# fiddle.net
KiCad netlist of a schematic drawn in EAGLE
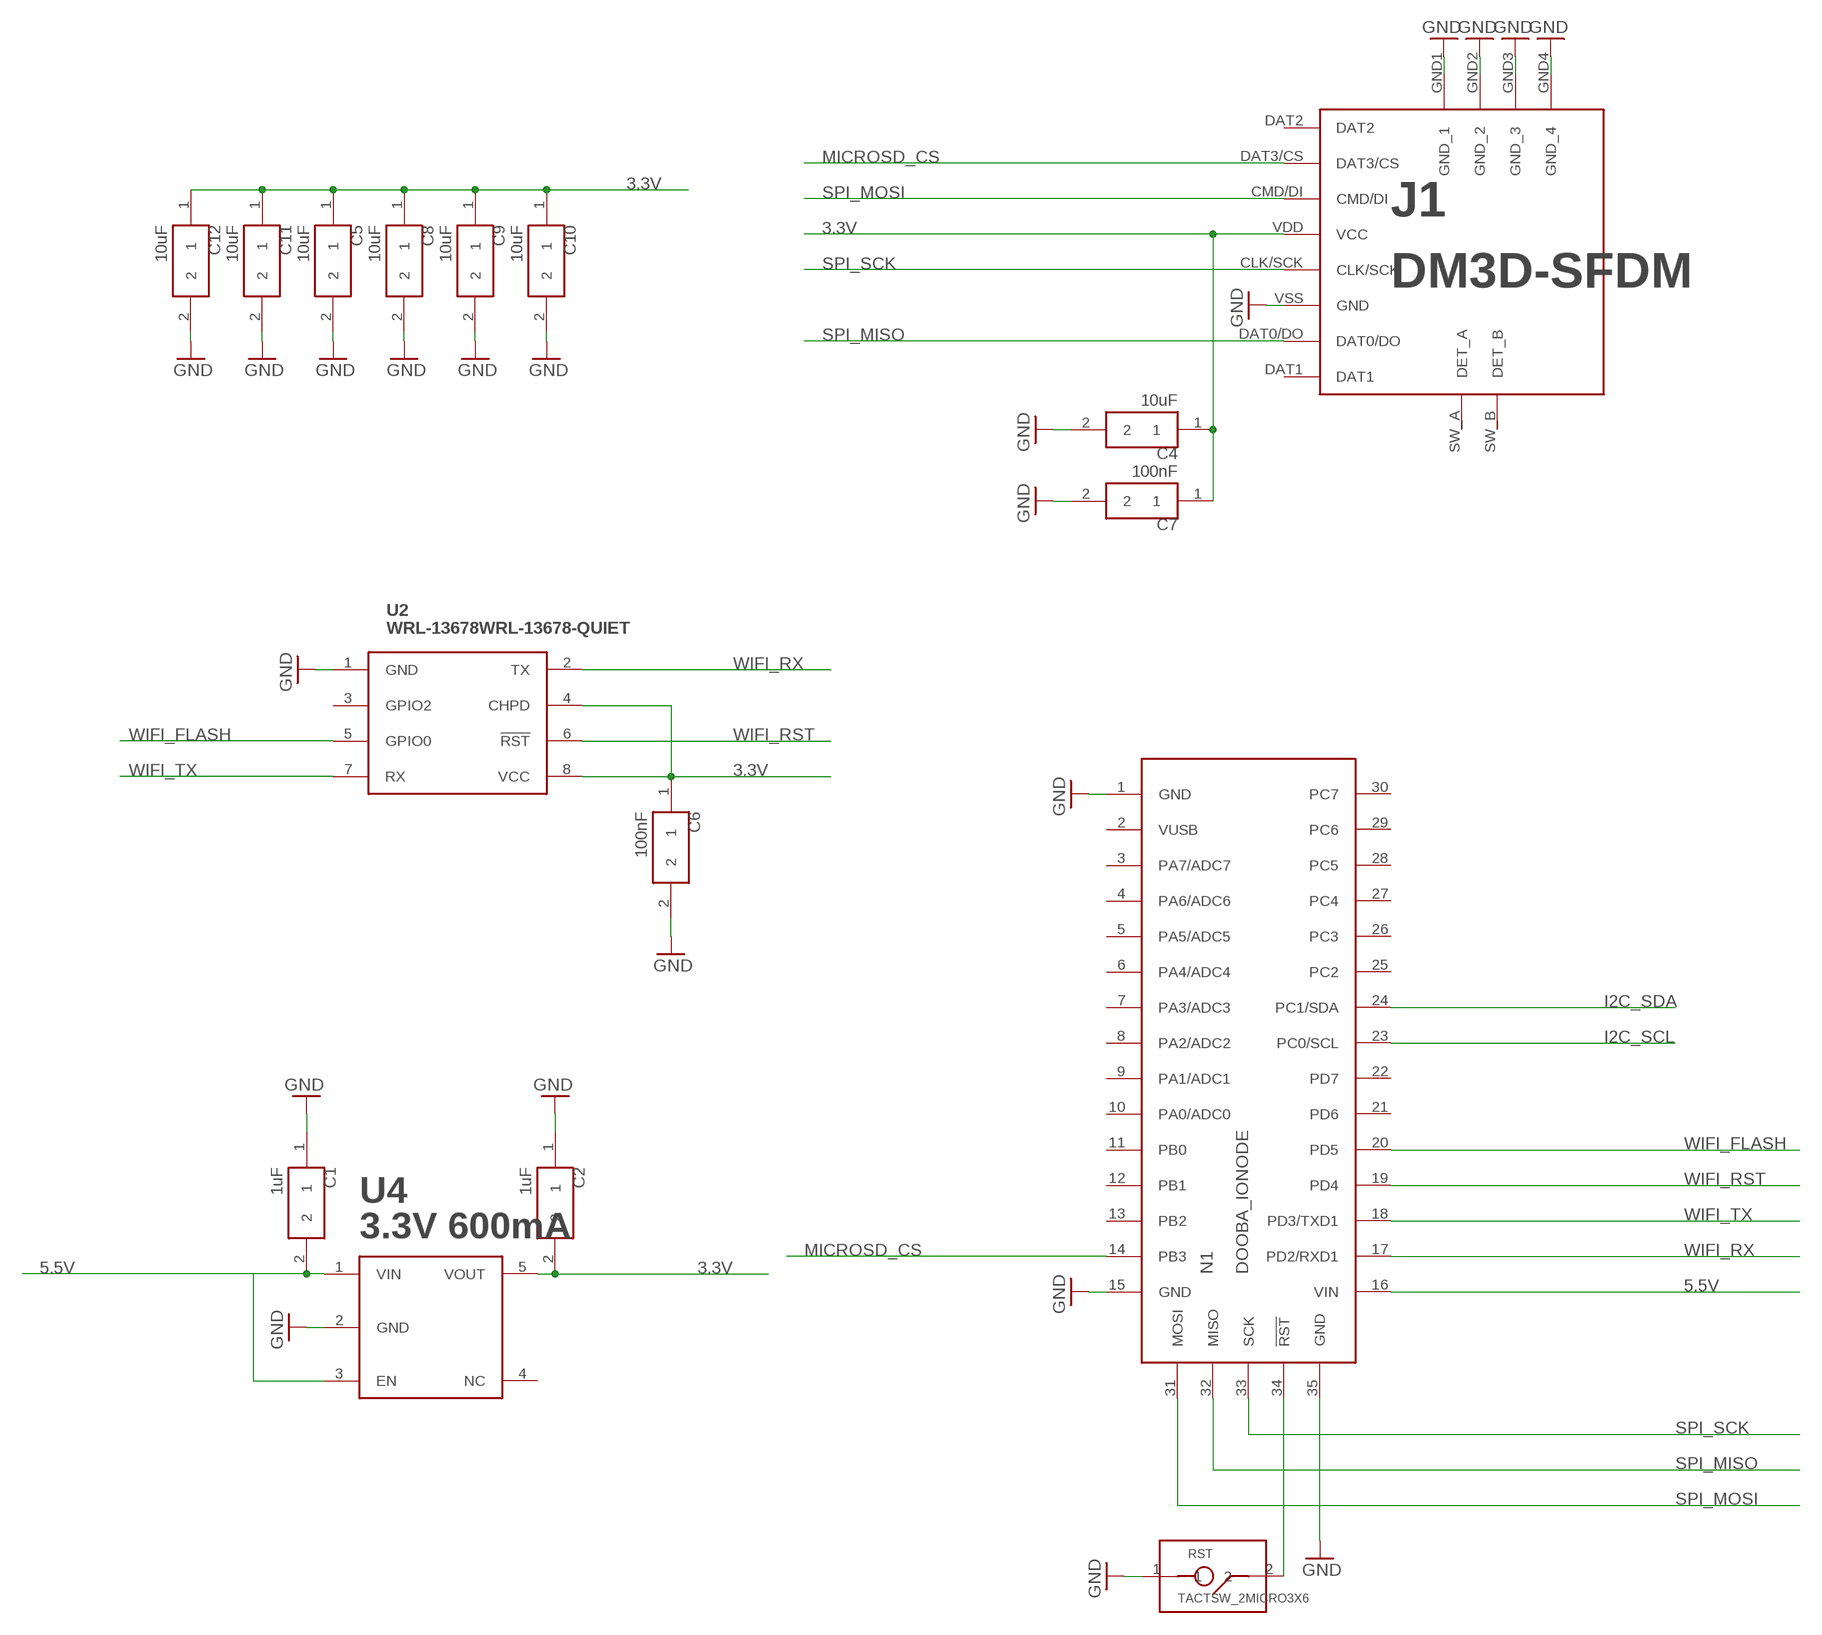
[diagram p0: schematic, sheet 1, part 1 of 2]
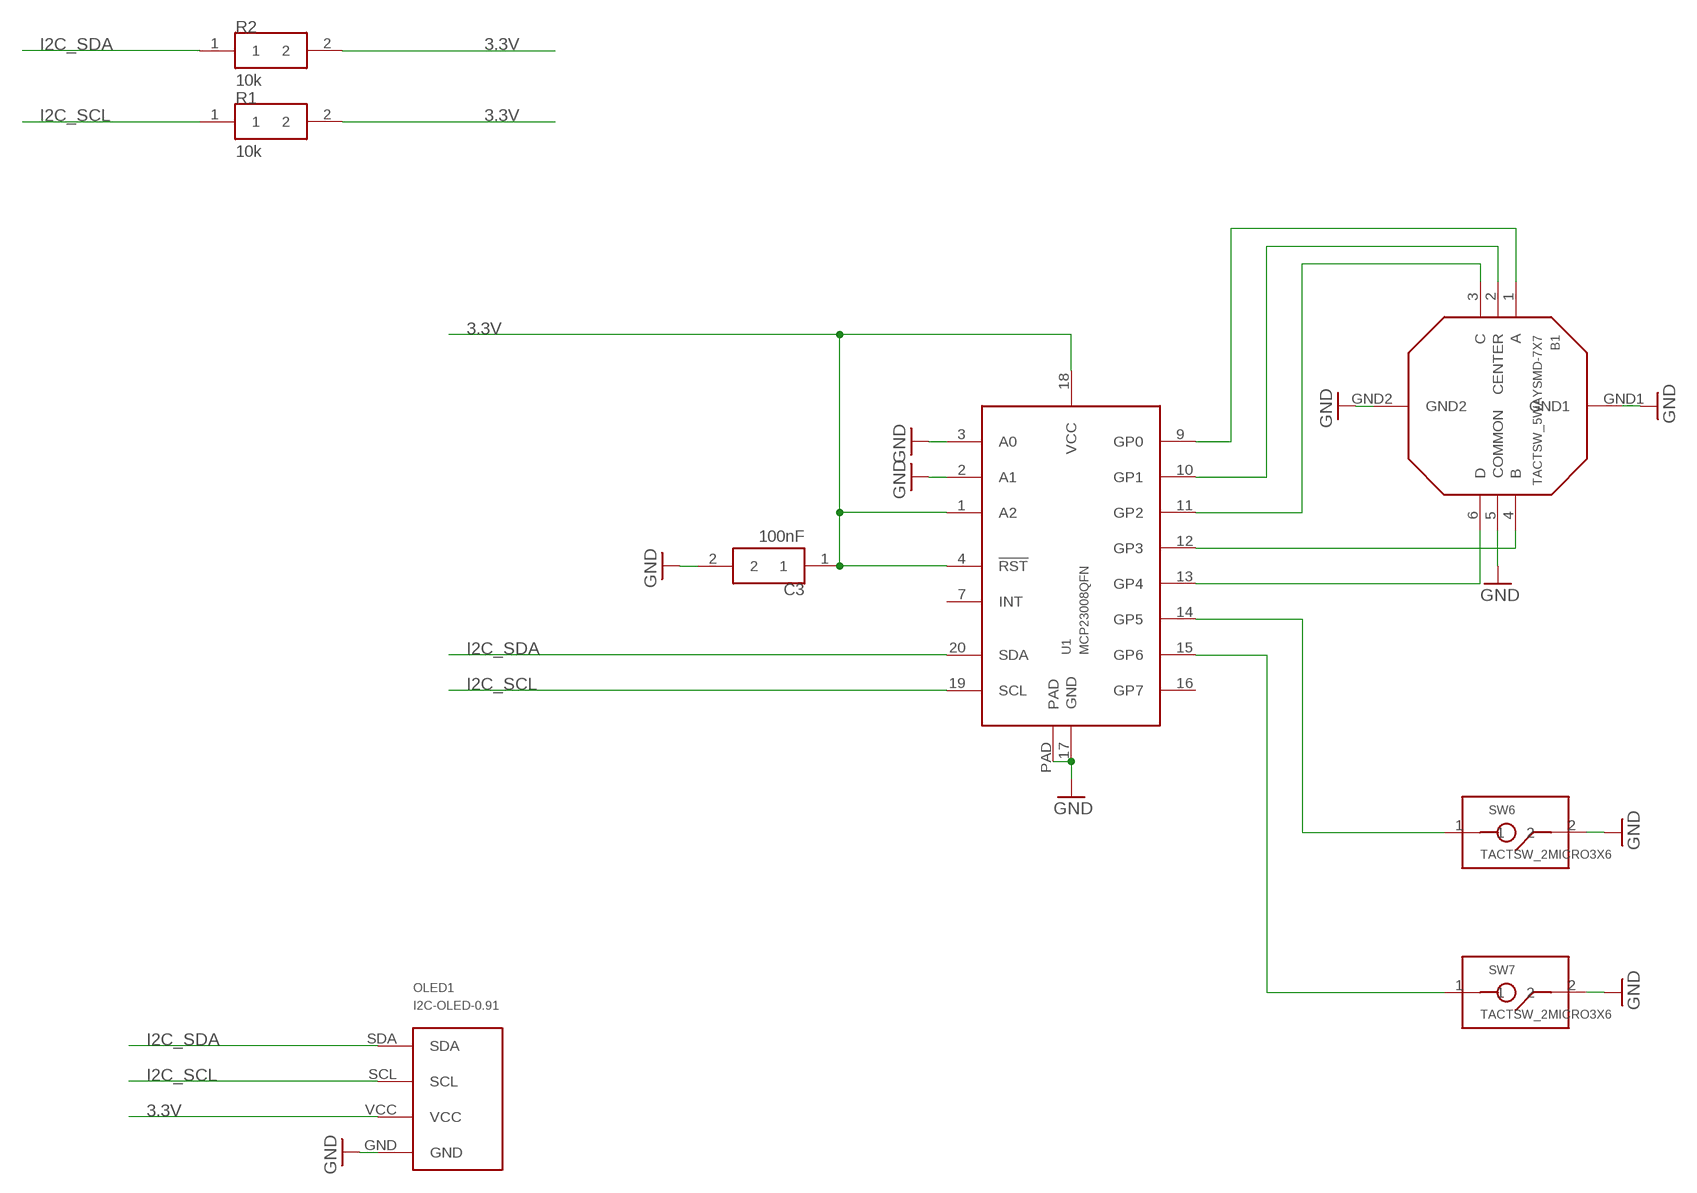
[diagram p1: schematic, sheet 1, part 2 of 2]

(export (version "E")
  (design (tool "Eeschema 10.0.6"))
  (components
    (comp (ref "B1")
      (value "TACTSW_5WAYSMD-7X7")
      (footprint "eagle-import:TACTSW-5WAY-7X7")
      (libsource (lib "eagle-import") (part "TACTSW_5WAYSMD-7X7"))
    )
    (comp (ref "C1")
      (value "1uF")
      (footprint "eagle-import:0805")
      (libsource (lib "eagle-import") (part "CAP0805"))
    )
    (comp (ref "C2")
      (value "1uF")
      (footprint "eagle-import:0805")
      (libsource (lib "eagle-import") (part "CAP0805"))
    )
    (comp (ref "C3")
      (value "100nF")
      (footprint "eagle-import:0805")
      (libsource (lib "eagle-import") (part "CAP0805"))
    )
    (comp (ref "C4")
      (value "10uF")
      (footprint "eagle-import:0805")
      (libsource (lib "eagle-import") (part "CAP0805"))
    )
    (comp (ref "C5")
      (value "10uF")
      (footprint "eagle-import:0805")
      (libsource (lib "eagle-import") (part "CAP0805"))
    )
    (comp (ref "C6")
      (value "100nF")
      (footprint "eagle-import:0805")
      (libsource (lib "eagle-import") (part "CAP0805"))
    )
    (comp (ref "C7")
      (value "100nF")
      (footprint "eagle-import:0805")
      (libsource (lib "eagle-import") (part "CAP0805"))
    )
    (comp (ref "C8")
      (value "10uF")
      (footprint "eagle-import:0805")
      (libsource (lib "eagle-import") (part "CAP0805"))
    )
    (comp (ref "C9")
      (value "10uF")
      (footprint "eagle-import:0805")
      (libsource (lib "eagle-import") (part "CAP0805"))
    )
    (comp (ref "C10")
      (value "10uF")
      (footprint "eagle-import:0805")
      (libsource (lib "eagle-import") (part "CAP0805"))
    )
    (comp (ref "C11")
      (value "10uF")
      (footprint "eagle-import:0805")
      (libsource (lib "eagle-import") (part "CAP0805"))
    )
    (comp (ref "C12")
      (value "10uF")
      (footprint "eagle-import:0805")
      (libsource (lib "eagle-import") (part "CAP0805"))
    )
    (comp (ref "J1")
      (value "DM3D-SFDM")
      (footprint "eagle-import:DM3D-SF")
      (libsource (lib "eagle-import") (part "DM3D-SFDM"))
    )
    (comp (ref "N1")
      (value "DOOBA_IONODE")
      (footprint "eagle-import:DOOBA_IONODE")
      (libsource (lib "eagle-import") (part "DOOBA_IONODE"))
    )
    (comp (ref "OLED1")
      (value "I2C-OLED-0.91")
      (footprint "eagle-import:I2C-OLED-0.91")
      (libsource (lib "eagle-import") (part "I2C-OLED-0.91"))
    )
    (comp (ref "R1")
      (value "10k")
      (footprint "eagle-import:0805")
      (libsource (lib "eagle-import") (part "RES0805"))
    )
    (comp (ref "R2")
      (value "10k")
      (footprint "eagle-import:0805")
      (libsource (lib "eagle-import") (part "RES0805"))
    )
    (comp (ref "RST")
      (value "TACTSW_2MICRO3X6")
      (footprint "eagle-import:TACTSW_MICRO3X6")
      (libsource (lib "eagle-import") (part "TACTSW_2MICRO3X6"))
    )
    (comp (ref "SW6")
      (value "TACTSW_2MICRO3X6")
      (footprint "eagle-import:TACTSW_MICRO3X6")
      (libsource (lib "eagle-import") (part "TACTSW_2MICRO3X6"))
    )
    (comp (ref "SW7")
      (value "TACTSW_2MICRO3X6")
      (footprint "eagle-import:TACTSW_MICRO3X6")
      (libsource (lib "eagle-import") (part "TACTSW_2MICRO3X6"))
    )
    (comp (ref "U1")
      (value "MCP23008QFN")
      (footprint "eagle-import:20-VQFN")
      (libsource (lib "eagle-import") (part "MCP23008QFN"))
    )
    (comp (ref "U2")
      (value "WRL-13678WRL-13678-QUIET")
      (footprint "eagle-import:WRL-13678-QUIET")
      (libsource (lib "eagle-import") (part "WRL-13678WRL-13678-QUIET"))
    )
    (comp (ref "U4")
      (value "3.3V 600mA")
      (footprint "eagle-import:SOT23-5")
      (libsource (lib "eagle-import") (part "LP3985SOT23-5"))
    )
  )
  (nets
    (net (code "1") (name "/3.3V") (class "Default")
      (node (ref "C10") (pin "1") (pinfunction "1_1") (pintype "bidirectional"))
      (node (ref "C11") (pin "1") (pinfunction "1_1") (pintype "bidirectional"))
      (node (ref "C12") (pin "1") (pinfunction "1_1") (pintype "bidirectional"))
      (node (ref "C2") (pin "2") (pinfunction "2_2") (pintype "bidirectional"))
      (node (ref "C3") (pin "1") (pinfunction "1_1") (pintype "bidirectional"))
      (node (ref "C4") (pin "1") (pinfunction "1_1") (pintype "bidirectional"))
      (node (ref "C5") (pin "1") (pinfunction "1_1") (pintype "bidirectional"))
      (node (ref "C6") (pin "1") (pinfunction "1_1") (pintype "bidirectional"))
      (node (ref "C7") (pin "1") (pinfunction "1_1") (pintype "bidirectional"))
      (node (ref "C8") (pin "1") (pinfunction "1_1") (pintype "bidirectional"))
      (node (ref "C9") (pin "1") (pinfunction "1_1") (pintype "bidirectional"))
      (node (ref "J1") (pin "VDD") (pinfunction "VCC_VDD") (pintype "bidirectional"))
      (node (ref "OLED1") (pin "VCC") (pinfunction "VCC_VCC") (pintype "bidirectional"))
      (node (ref "R1") (pin "2") (pinfunction "2_2") (pintype "bidirectional"))
      (node (ref "R2") (pin "2") (pinfunction "2_2") (pintype "bidirectional"))
      (node (ref "U1") (pin "1") (pinfunction "A2_1") (pintype "bidirectional"))
      (node (ref "U1") (pin "18") (pinfunction "VCC_18") (pintype "bidirectional"))
      (node (ref "U1") (pin "4") (pinfunction "~{RST}_4") (pintype "bidirectional"))
      (node (ref "U2") (pin "4") (pinfunction "CHPD_4") (pintype "bidirectional"))
      (node (ref "U2") (pin "8") (pinfunction "VCC_8") (pintype "bidirectional"))
      (node (ref "U4") (pin "5") (pinfunction "VOUT_5") (pintype "bidirectional"))
    )
    (net (code "2") (name "/5.5V") (class "Default")
      (node (ref "C1") (pin "2") (pinfunction "2_2") (pintype "bidirectional"))
      (node (ref "N1") (pin "16") (pinfunction "VIN_16") (pintype "bidirectional"))
      (node (ref "U4") (pin "1") (pinfunction "VIN_1") (pintype "bidirectional"))
      (node (ref "U4") (pin "3") (pinfunction "EN_3") (pintype "bidirectional"))
    )
    (net (code "3") (name "/I2C_SCL") (class "Default")
      (node (ref "N1") (pin "23") (pinfunction "PC0/SCL_23") (pintype "bidirectional"))
      (node (ref "OLED1") (pin "SCL") (pinfunction "SCL_SCL") (pintype "bidirectional"))
      (node (ref "R1") (pin "1") (pinfunction "1_1") (pintype "bidirectional"))
      (node (ref "U1") (pin "19") (pinfunction "SCL_19") (pintype "bidirectional"))
    )
    (net (code "4") (name "/I2C_SDA") (class "Default")
      (node (ref "N1") (pin "24") (pinfunction "PC1/SDA_24") (pintype "bidirectional"))
      (node (ref "OLED1") (pin "SDA") (pinfunction "SDA_SDA") (pintype "bidirectional"))
      (node (ref "R2") (pin "1") (pinfunction "1_1") (pintype "bidirectional"))
      (node (ref "U1") (pin "20") (pinfunction "SDA_20") (pintype "bidirectional"))
    )
    (net (code "5") (name "/MICROSD_CS") (class "Default")
      (node (ref "J1") (pin "DAT3/CS") (pinfunction "DAT3/CS_DAT3/CS") (pintype "bidirectional"))
      (node (ref "N1") (pin "14") (pinfunction "PB3_14") (pintype "bidirectional"))
    )
    (net (code "6") (name "/SPI_MISO") (class "Default")
      (node (ref "J1") (pin "DAT0/DO") (pinfunction "DAT0/DO_DAT0/DO") (pintype "bidirectional"))
      (node (ref "N1") (pin "32") (pinfunction "MISO_32") (pintype "bidirectional"))
    )
    (net (code "7") (name "/SPI_MOSI") (class "Default")
      (node (ref "J1") (pin "CMD/DI") (pinfunction "CMD/DI_CMD/DI") (pintype "bidirectional"))
      (node (ref "N1") (pin "31") (pinfunction "MOSI_31") (pintype "bidirectional"))
    )
    (net (code "8") (name "/SPI_SCK") (class "Default")
      (node (ref "J1") (pin "CLK/SCK") (pinfunction "CLK/SCK_CLK/SCK") (pintype "bidirectional"))
      (node (ref "N1") (pin "33") (pinfunction "SCK_33") (pintype "bidirectional"))
    )
    (net (code "9") (name "/WIFI_FLASH") (class "Default")
      (node (ref "N1") (pin "20") (pinfunction "PD5_20") (pintype "bidirectional"))
      (node (ref "U2") (pin "5") (pinfunction "GPIO0_5") (pintype "bidirectional"))
    )
    (net (code "10") (name "/WIFI_RST") (class "Default")
      (node (ref "N1") (pin "19") (pinfunction "PD4_19") (pintype "bidirectional"))
      (node (ref "U2") (pin "6") (pinfunction "~{RST}_6") (pintype "bidirectional"))
    )
    (net (code "11") (name "/WIFI_RX") (class "Default")
      (node (ref "N1") (pin "17") (pinfunction "PD2/RXD1_17") (pintype "bidirectional"))
      (node (ref "U2") (pin "2") (pinfunction "TX_2") (pintype "bidirectional"))
    )
    (net (code "12") (name "/WIFI_TX") (class "Default")
      (node (ref "N1") (pin "18") (pinfunction "PD3/TXD1_18") (pintype "bidirectional"))
      (node (ref "U2") (pin "7") (pinfunction "RX_7") (pintype "bidirectional"))
    )
    (net (code "13") (name "GND") (class "Default")
      (node (ref "B1") (pin "5") (pinfunction "COMMON_5") (pintype "bidirectional"))
      (node (ref "B1") (pin "GND1") (pinfunction "GND1_GND1") (pintype "bidirectional"))
      (node (ref "B1") (pin "GND2") (pinfunction "GND2_GND2") (pintype "bidirectional"))
      (node (ref "C1") (pin "1") (pinfunction "1_1") (pintype "bidirectional"))
      (node (ref "C10") (pin "2") (pinfunction "2_2") (pintype "bidirectional"))
      (node (ref "C11") (pin "2") (pinfunction "2_2") (pintype "bidirectional"))
      (node (ref "C12") (pin "2") (pinfunction "2_2") (pintype "bidirectional"))
      (node (ref "C2") (pin "1") (pinfunction "1_1") (pintype "bidirectional"))
      (node (ref "C3") (pin "2") (pinfunction "2_2") (pintype "bidirectional"))
      (node (ref "C4") (pin "2") (pinfunction "2_2") (pintype "bidirectional"))
      (node (ref "C5") (pin "2") (pinfunction "2_2") (pintype "bidirectional"))
      (node (ref "C6") (pin "2") (pinfunction "2_2") (pintype "bidirectional"))
      (node (ref "C7") (pin "2") (pinfunction "2_2") (pintype "bidirectional"))
      (node (ref "C8") (pin "2") (pinfunction "2_2") (pintype "bidirectional"))
      (node (ref "C9") (pin "2") (pinfunction "2_2") (pintype "bidirectional"))
      (node (ref "J1") (pin "GND1") (pinfunction "GND_1_GND1") (pintype "bidirectional"))
      (node (ref "J1") (pin "GND2") (pinfunction "GND_2_GND2") (pintype "bidirectional"))
      (node (ref "J1") (pin "GND3") (pinfunction "GND_3_GND3") (pintype "bidirectional"))
      (node (ref "J1") (pin "GND4") (pinfunction "GND_4_GND4") (pintype "bidirectional"))
      (node (ref "J1") (pin "VSS") (pinfunction "GND_VSS") (pintype "bidirectional"))
      (node (ref "N1") (pin "1") (pinfunction "GND_1") (pintype "bidirectional"))
      (node (ref "N1") (pin "15") (pinfunction "GND_15") (pintype "bidirectional"))
      (node (ref "N1") (pin "35") (pinfunction "GND_35") (pintype "bidirectional"))
      (node (ref "OLED1") (pin "GND") (pinfunction "GND_GND") (pintype "bidirectional"))
      (node (ref "RST") (pin "1") (pinfunction "1_1") (pintype "bidirectional"))
      (node (ref "SW6") (pin "2") (pinfunction "2_2") (pintype "bidirectional"))
      (node (ref "SW7") (pin "2") (pinfunction "2_2") (pintype "bidirectional"))
      (node (ref "U1") (pin "17") (pinfunction "GND_17") (pintype "bidirectional"))
      (node (ref "U1") (pin "2") (pinfunction "A1_2") (pintype "bidirectional"))
      (node (ref "U1") (pin "3") (pinfunction "A0_3") (pintype "bidirectional"))
      (node (ref "U1") (pin "PAD") (pinfunction "PAD_PAD") (pintype "bidirectional"))
      (node (ref "U2") (pin "1") (pinfunction "GND_1") (pintype "bidirectional"))
      (node (ref "U4") (pin "2") (pinfunction "GND_2") (pintype "bidirectional"))
    )
    (net (code "14") (name "Net-(B1-A)") (class "Default")
      (node (ref "B1") (pin "1") (pinfunction "A_1") (pintype "bidirectional"))
      (node (ref "U1") (pin "9") (pinfunction "GP0_9") (pintype "bidirectional"))
    )
    (net (code "15") (name "Net-(B1-B)") (class "Default")
      (node (ref "B1") (pin "4") (pinfunction "B_4") (pintype "bidirectional"))
      (node (ref "U1") (pin "12") (pinfunction "GP3_12") (pintype "bidirectional"))
    )
    (net (code "16") (name "Net-(B1-C)") (class "Default")
      (node (ref "B1") (pin "3") (pinfunction "C_3") (pintype "bidirectional"))
      (node (ref "U1") (pin "11") (pinfunction "GP2_11") (pintype "bidirectional"))
    )
    (net (code "17") (name "Net-(B1-CENTER)") (class "Default")
      (node (ref "B1") (pin "2") (pinfunction "CENTER_2") (pintype "bidirectional"))
      (node (ref "U1") (pin "10") (pinfunction "GP1_10") (pintype "bidirectional"))
    )
    (net (code "18") (name "Net-(B1-D)") (class "Default")
      (node (ref "B1") (pin "6") (pinfunction "D_6") (pintype "bidirectional"))
      (node (ref "U1") (pin "13") (pinfunction "GP4_13") (pintype "bidirectional"))
    )
    (net (code "19") (name "Net-(N1-~{RST})") (class "Default")
      (node (ref "N1") (pin "34") (pinfunction "~{RST}_34") (pintype "bidirectional"))
      (node (ref "RST") (pin "2") (pinfunction "2_2") (pintype "bidirectional"))
    )
    (net (code "20") (name "Net-(U1-GP5)") (class "Default")
      (node (ref "SW6") (pin "1") (pinfunction "1_1") (pintype "bidirectional"))
      (node (ref "U1") (pin "14") (pinfunction "GP5_14") (pintype "bidirectional"))
    )
    (net (code "21") (name "Net-(U1-GP6)") (class "Default")
      (node (ref "SW7") (pin "1") (pinfunction "1_1") (pintype "bidirectional"))
      (node (ref "U1") (pin "15") (pinfunction "GP6_15") (pintype "bidirectional"))
    )
    (net (code "22") (name "unconnected-(J1-DET_A-PadSW_A)") (class "Default")
      (node (ref "J1") (pin "SW_A") (pinfunction "DET_A_SW_A") (pintype "bidirectional"))
    )
    (net (code "23") (name "unconnected-(J1-DET_B-PadSW_B)") (class "Default")
      (node (ref "J1") (pin "SW_B") (pinfunction "DET_B_SW_B") (pintype "bidirectional"))
    )
    (net (code "24") (name "unconnected-(J1-PadDAT1)") (class "Default")
      (node (ref "J1") (pin "DAT1") (pinfunction "DAT1_DAT1") (pintype "bidirectional"))
    )
    (net (code "25") (name "unconnected-(J1-PadDAT2)") (class "Default")
      (node (ref "J1") (pin "DAT2") (pinfunction "DAT2_DAT2") (pintype "bidirectional"))
    )
    (net (code "26") (name "unconnected-(N1-PA0{slash}ADC0-Pad10)") (class "Default")
      (node (ref "N1") (pin "10") (pinfunction "PA0/ADC0_10") (pintype "bidirectional"))
    )
    (net (code "27") (name "unconnected-(N1-PA1{slash}ADC1-Pad9)") (class "Default")
      (node (ref "N1") (pin "9") (pinfunction "PA1/ADC1_9") (pintype "bidirectional"))
    )
    (net (code "28") (name "unconnected-(N1-PA2{slash}ADC2-Pad8)") (class "Default")
      (node (ref "N1") (pin "8") (pinfunction "PA2/ADC2_8") (pintype "bidirectional"))
    )
    (net (code "29") (name "unconnected-(N1-PA3{slash}ADC3-Pad7)") (class "Default")
      (node (ref "N1") (pin "7") (pinfunction "PA3/ADC3_7") (pintype "bidirectional"))
    )
    (net (code "30") (name "unconnected-(N1-PA4{slash}ADC4-Pad6)") (class "Default")
      (node (ref "N1") (pin "6") (pinfunction "PA4/ADC4_6") (pintype "bidirectional"))
    )
    (net (code "31") (name "unconnected-(N1-PA5{slash}ADC5-Pad5)") (class "Default")
      (node (ref "N1") (pin "5") (pinfunction "PA5/ADC5_5") (pintype "bidirectional"))
    )
    (net (code "32") (name "unconnected-(N1-PA6{slash}ADC6-Pad4)") (class "Default")
      (node (ref "N1") (pin "4") (pinfunction "PA6/ADC6_4") (pintype "bidirectional"))
    )
    (net (code "33") (name "unconnected-(N1-PA7{slash}ADC7-Pad3)") (class "Default")
      (node (ref "N1") (pin "3") (pinfunction "PA7/ADC7_3") (pintype "bidirectional"))
    )
    (net (code "34") (name "unconnected-(N1-PB0-Pad11)") (class "Default")
      (node (ref "N1") (pin "11") (pinfunction "PB0_11") (pintype "bidirectional"))
    )
    (net (code "35") (name "unconnected-(N1-PB1-Pad12)") (class "Default")
      (node (ref "N1") (pin "12") (pinfunction "PB1_12") (pintype "bidirectional"))
    )
    (net (code "36") (name "unconnected-(N1-PB2-Pad13)") (class "Default")
      (node (ref "N1") (pin "13") (pinfunction "PB2_13") (pintype "bidirectional"))
    )
    (net (code "37") (name "unconnected-(N1-PC2-Pad25)") (class "Default")
      (node (ref "N1") (pin "25") (pinfunction "PC2_25") (pintype "bidirectional"))
    )
    (net (code "38") (name "unconnected-(N1-PC3-Pad26)") (class "Default")
      (node (ref "N1") (pin "26") (pinfunction "PC3_26") (pintype "bidirectional"))
    )
    (net (code "39") (name "unconnected-(N1-PC4-Pad27)") (class "Default")
      (node (ref "N1") (pin "27") (pinfunction "PC4_27") (pintype "bidirectional"))
    )
    (net (code "40") (name "unconnected-(N1-PC5-Pad28)") (class "Default")
      (node (ref "N1") (pin "28") (pinfunction "PC5_28") (pintype "bidirectional"))
    )
    (net (code "41") (name "unconnected-(N1-PC6-Pad29)") (class "Default")
      (node (ref "N1") (pin "29") (pinfunction "PC6_29") (pintype "bidirectional"))
    )
    (net (code "42") (name "unconnected-(N1-PC7-Pad30)") (class "Default")
      (node (ref "N1") (pin "30") (pinfunction "PC7_30") (pintype "bidirectional"))
    )
    (net (code "43") (name "unconnected-(N1-PD6-Pad21)") (class "Default")
      (node (ref "N1") (pin "21") (pinfunction "PD6_21") (pintype "bidirectional"))
    )
    (net (code "44") (name "unconnected-(N1-PD7-Pad22)") (class "Default")
      (node (ref "N1") (pin "22") (pinfunction "PD7_22") (pintype "bidirectional"))
    )
    (net (code "45") (name "unconnected-(N1-VUSB-Pad2)") (class "Default")
      (node (ref "N1") (pin "2") (pinfunction "VUSB_2") (pintype "bidirectional"))
    )
    (net (code "46") (name "unconnected-(U1-GP7-Pad16)") (class "Default")
      (node (ref "U1") (pin "16") (pinfunction "GP7_16") (pintype "bidirectional"))
    )
    (net (code "47") (name "unconnected-(U1-INT-Pad7)") (class "Default")
      (node (ref "U1") (pin "7") (pinfunction "INT_7") (pintype "bidirectional"))
    )
    (net (code "48") (name "unconnected-(U2-GPIO2-Pad3)") (class "Default")
      (node (ref "U2") (pin "3") (pinfunction "GPIO2_3") (pintype "bidirectional"))
    )
    (net (code "49") (name "unconnected-(U4-NC-Pad4)") (class "Default")
      (node (ref "U4") (pin "4") (pinfunction "NC_4") (pintype "bidirectional"))
    )
  )
)
